# ADC.net
KiCad netlist of a schematic drawn in Altium Designer
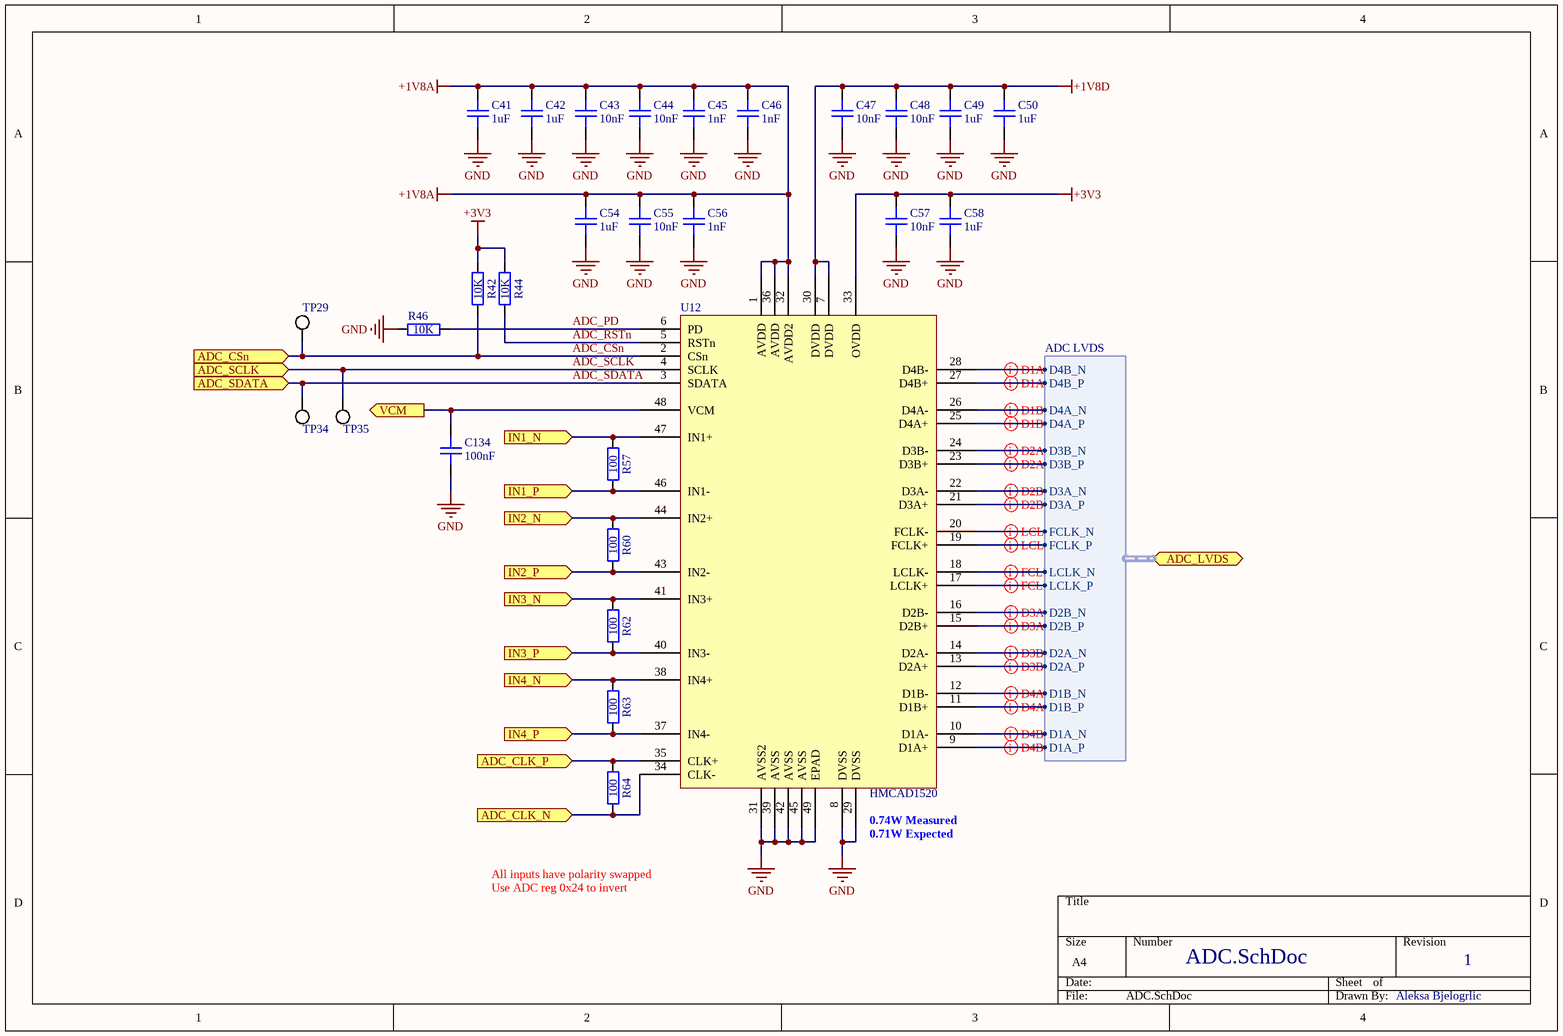
[diagram p0: ADC.SchDoc]

(export (version "E")
  (design (tool "Eeschema 10.0.6"))
  (components
    (comp (ref "C41")
      (value "1uF")
      (footprint "GEN_C_0402")
      (fields
        (field (name "MANUFACTURER") "Murata")
        (field (name "MANUFACTURER PART NUMBER") "GRM155R61E105KA12D")
      )
      (libsource (lib "DSO") (part "CAP 1uF 25V X5R 0402"))
    )
    (comp (ref "C42")
      (value "1uF")
      (footprint "GEN_C_0402")
      (fields
        (field (name "MANUFACTURER") "Murata")
        (field (name "MANUFACTURER PART NUMBER") "GRM155R61E105KA12D")
      )
      (libsource (lib "DSO") (part "CAP 1uF 25V X5R 0402"))
    )
    (comp (ref "C43")
      (value "10nF")
      (footprint "GEN_C_0402")
      (fields
        (field (name "HOUSE PART NUMBER") "C-10nF-0402-002")
        (field (name "MANUFACTURER") "Murata")
        (field (name "MANUFACTURER PART NUMBER") "GRM155R71H103KA88J")
      )
      (libsource (lib "DSO") (part "CAP 10nF 50V X7R 0402"))
    )
    (comp (ref "C44")
      (value "10nF")
      (footprint "GEN_C_0402")
      (fields
        (field (name "HOUSE PART NUMBER") "C-10nF-0402-002")
        (field (name "MANUFACTURER") "Murata")
        (field (name "MANUFACTURER PART NUMBER") "GRM155R71H103KA88J")
      )
      (libsource (lib "DSO") (part "CAP 10nF 50V X7R 0402"))
    )
    (comp (ref "C45")
      (value "1nF")
      (footprint "GEN_C_0402")
      (fields
        (field (name "MANUFACTURER") "Murata")
        (field (name "MANUFACTURER PART NUMBER") "GRM1555C1H102FA01D")
      )
      (libsource (lib "DSO") (part "CAP 1nF 50V C0G 0402"))
    )
    (comp (ref "C46")
      (value "1nF")
      (footprint "GEN_C_0402")
      (fields
        (field (name "MANUFACTURER") "Murata")
        (field (name "MANUFACTURER PART NUMBER") "GRM1555C1H102FA01D")
      )
      (libsource (lib "DSO") (part "CAP 1nF 50V C0G 0402"))
    )
    (comp (ref "C47")
      (value "10nF")
      (footprint "GEN_C_0402")
      (fields
        (field (name "HOUSE PART NUMBER") "C-10nF-0402-002")
        (field (name "MANUFACTURER") "Murata")
        (field (name "MANUFACTURER PART NUMBER") "GRM155R71H103KA88J")
      )
      (libsource (lib "DSO") (part "CAP 10nF 50V X7R 0402"))
    )
    (comp (ref "C48")
      (value "10nF")
      (footprint "GEN_C_0402")
      (fields
        (field (name "HOUSE PART NUMBER") "C-10nF-0402-002")
        (field (name "MANUFACTURER") "Murata")
        (field (name "MANUFACTURER PART NUMBER") "GRM155R71H103KA88J")
      )
      (libsource (lib "DSO") (part "CAP 10nF 50V X7R 0402"))
    )
    (comp (ref "C49")
      (value "1uF")
      (footprint "GEN_C_0402")
      (fields
        (field (name "MANUFACTURER") "Murata")
        (field (name "MANUFACTURER PART NUMBER") "GRM155R61E105KA12D")
      )
      (libsource (lib "DSO") (part "CAP 1uF 25V X5R 0402"))
    )
    (comp (ref "C50")
      (value "1uF")
      (footprint "GEN_C_0402")
      (fields
        (field (name "MANUFACTURER") "Murata")
        (field (name "MANUFACTURER PART NUMBER") "GRM155R61E105KA12D")
      )
      (libsource (lib "DSO") (part "CAP 1uF 25V X5R 0402"))
    )
    (comp (ref "C54")
      (value "1uF")
      (footprint "GEN_C_0402")
      (fields
        (field (name "MANUFACTURER") "Murata")
        (field (name "MANUFACTURER PART NUMBER") "GRM155R61E105KA12D")
      )
      (libsource (lib "DSO") (part "CAP 1uF 25V X5R 0402"))
    )
    (comp (ref "C55")
      (value "10nF")
      (footprint "GEN_C_0402")
      (fields
        (field (name "HOUSE PART NUMBER") "C-10nF-0402-002")
        (field (name "MANUFACTURER") "Murata")
        (field (name "MANUFACTURER PART NUMBER") "GRM155R71H103KA88J")
      )
      (libsource (lib "DSO") (part "CAP 10nF 50V X7R 0402"))
    )
    (comp (ref "C56")
      (value "1nF")
      (footprint "GEN_C_0402")
      (fields
        (field (name "MANUFACTURER") "Murata")
        (field (name "MANUFACTURER PART NUMBER") "GRM1555C1H102FA01D")
      )
      (libsource (lib "DSO") (part "CAP 1nF 50V C0G 0402"))
    )
    (comp (ref "C57")
      (value "10nF")
      (footprint "GEN_C_0402")
      (fields
        (field (name "HOUSE PART NUMBER") "C-10nF-0402-002")
        (field (name "MANUFACTURER") "Murata")
        (field (name "MANUFACTURER PART NUMBER") "GRM155R71H103KA88J")
      )
      (libsource (lib "DSO") (part "CAP 10nF 50V X7R 0402"))
    )
    (comp (ref "C58")
      (value "1uF")
      (footprint "GEN_C_0402")
      (fields
        (field (name "MANUFACTURER") "Murata")
        (field (name "MANUFACTURER PART NUMBER") "GRM155R61E105KA12D")
      )
      (libsource (lib "DSO") (part "CAP 1uF 25V X5R 0402"))
    )
    (comp (ref "C134")
      (value "100nF")
      (footprint "GEN_C_0402")
      (fields
        (field (name "HOUSE PART NUMBER") "C-100nF-0402-002")
        (field (name "MANUFACTURER") "Murata")
        (field (name "MANUFACTURER PART NUMBER") "GCM155R71C104KA55D")
      )
      (libsource (lib "DSO") (part "CAP 100nF 16V X7R 0402"))
    )
    (comp (ref "R42")
      (value "10K")
      (footprint "GEN_R_0402")
      (fields
        (field (name "TOLERANCE") "1%")
        (field (name "MANUFACTURER") "Panasonic")
        (field (name "MANUFACTURER PART NUMBER") "ERJ-2RKF1002X")
      )
      (libsource (lib "DSO") (part "RES 10K OHM 1% 1/10W 0402"))
    )
    (comp (ref "R44")
      (value "10K")
      (footprint "GEN_R_0402")
      (fields
        (field (name "TOLERANCE") "1%")
        (field (name "MANUFACTURER") "Panasonic")
        (field (name "MANUFACTURER PART NUMBER") "ERJ-2RKF1002X")
      )
      (libsource (lib "DSO") (part "RES 10K OHM 1% 1/10W 0402"))
    )
    (comp (ref "R46")
      (value "10K")
      (footprint "GEN_R_0402")
      (fields
        (field (name "TOLERANCE") "1%")
        (field (name "MANUFACTURER") "Panasonic")
        (field (name "MANUFACTURER PART NUMBER") "ERJ-2RKF1002X")
      )
      (libsource (lib "") (part "RES 10K OHM 1% 1/10W 0402_1"))
    )
    (comp (ref "R57")
      (value "100")
      (footprint "GEN_R_0402")
      (fields
        (field (name "TOLERANCE") "1%")
        (field (name "MANUFACTURER") "Yageo")
        (field (name "MANUFACTURER PART NUMBER") "RC0402FR-07100RL")
      )
      (libsource (lib "DSO") (part "RES 100 OHM 1% 1/10W 0402"))
    )
    (comp (ref "R60")
      (value "100")
      (footprint "GEN_R_0402")
      (fields
        (field (name "TOLERANCE") "1%")
        (field (name "MANUFACTURER") "Yageo")
        (field (name "MANUFACTURER PART NUMBER") "RC0402FR-07100RL")
      )
      (libsource (lib "DSO") (part "RES 100 OHM 1% 1/10W 0402"))
    )
    (comp (ref "R62")
      (value "100")
      (footprint "GEN_R_0402")
      (fields
        (field (name "TOLERANCE") "1%")
        (field (name "MANUFACTURER") "Yageo")
        (field (name "MANUFACTURER PART NUMBER") "RC0402FR-07100RL")
      )
      (libsource (lib "DSO") (part "RES 100 OHM 1% 1/10W 0402"))
    )
    (comp (ref "R63")
      (value "100")
      (footprint "GEN_R_0402")
      (fields
        (field (name "TOLERANCE") "1%")
        (field (name "MANUFACTURER") "Yageo")
        (field (name "MANUFACTURER PART NUMBER") "RC0402FR-07100RL")
      )
      (libsource (lib "DSO") (part "RES 100 OHM 1% 1/10W 0402"))
    )
    (comp (ref "R64")
      (value "100")
      (footprint "GEN_R_0402")
      (fields
        (field (name "TOLERANCE") "1%")
        (field (name "MANUFACTURER") "Yageo")
        (field (name "MANUFACTURER PART NUMBER") "RC0402FR-07100RL")
      )
      (libsource (lib "DSO") (part "RES 100 OHM 1% 1/10W 0402"))
    )
    (comp (ref "TP29") (value "PCB") (footprint "GEN_TP_PCB") (libsource (lib "DSO") (part "TP PCB 1mm")))
    (comp (ref "TP34") (value "PCB") (footprint "GEN_TP_PCB") (libsource (lib "DSO") (part "TP PCB 1mm")))
    (comp (ref "TP35") (value "PCB") (footprint "GEN_TP_PCB") (libsource (lib "DSO") (part "TP PCB 1mm")))
    (comp (ref "U12")
      (value "HMCAD1520")
      (footprint "AD_QFN48_LP7")
      (fields (field (name "MANUFACTURER") "Analog Devices"))
      (libsource (lib "DSO") (part "IC ADC HMCAD1520"))
    )
  )
  (nets
    (net (code "3") (name "+1V8A") (class "Default")
      (node (ref "C41") (pin "2") (pinfunction "2_2") (pintype "passive"))
      (node (ref "C42") (pin "2") (pinfunction "2_2") (pintype "passive"))
      (node (ref "C43") (pin "2") (pinfunction "2_2") (pintype "passive"))
      (node (ref "C44") (pin "2") (pinfunction "2_2") (pintype "passive"))
      (node (ref "C45") (pin "2") (pinfunction "2_2") (pintype "passive"))
      (node (ref "C46") (pin "2") (pinfunction "2_2") (pintype "passive"))
      (node (ref "C54") (pin "2") (pinfunction "2_2") (pintype "passive"))
      (node (ref "C55") (pin "2") (pinfunction "2_2") (pintype "passive"))
      (node (ref "C56") (pin "2") (pinfunction "2_2") (pintype "passive"))
      (node (ref "U12") (pin "1") (pinfunction "AVDD_1") (pintype "passive"))
      (node (ref "U12") (pin "32") (pinfunction "AVDD2_32") (pintype "passive"))
      (node (ref "U12") (pin "36") (pinfunction "AVDD_36") (pintype "passive"))
    )
    (net (code "4") (name "+1V8D") (class "Default")
      (node (ref "C47") (pin "2") (pinfunction "2_2") (pintype "passive"))
      (node (ref "C48") (pin "2") (pinfunction "2_2") (pintype "passive"))
      (node (ref "C49") (pin "2") (pinfunction "2_2") (pintype "passive"))
      (node (ref "C50") (pin "2") (pinfunction "2_2") (pintype "passive"))
      (node (ref "U12") (pin "30") (pinfunction "DVDD_30") (pintype "passive"))
      (node (ref "U12") (pin "7") (pinfunction "DVDD_7") (pintype "passive"))
    )
    (net (code "5") (name "+3V3") (class "Default")
      (node (ref "C57") (pin "2") (pinfunction "2_2") (pintype "passive"))
      (node (ref "C58") (pin "2") (pinfunction "2_2") (pintype "passive"))
      (node (ref "R42") (pin "2") (pinfunction "2_2") (pintype "passive"))
      (node (ref "R44") (pin "2") (pinfunction "2_2") (pintype "passive"))
      (node (ref "U12") (pin "33") (pinfunction "OVDD_33") (pintype "passive"))
    )
    (net (code "6") (name "/ADC_CLK_N") (class "Default")
      (node (ref "R64") (pin "1") (pinfunction "1_1") (pintype "passive"))
      (node (ref "U12") (pin "34") (pinfunction "CLK-_34") (pintype "passive"))
    )
    (net (code "7") (name "/ADC_CLK_P") (class "Default")
      (node (ref "R64") (pin "2") (pinfunction "2_2") (pintype "passive"))
      (node (ref "U12") (pin "35") (pinfunction "CLK+_35") (pintype "passive"))
    )
    (net (code "8") (name "/ADC_CSn") (class "Default")
      (node (ref "R42") (pin "1") (pinfunction "1_1") (pintype "passive"))
      (node (ref "TP29") (pin "1") (pinfunction "1_1") (pintype "passive"))
      (node (ref "U12") (pin "2") (pinfunction "CSn_2") (pintype "passive"))
    )
    (net (code "9") (name "/ADC_PD") (class "Default")
      (node (ref "R46") (pin "1") (pinfunction "1_1") (pintype "passive"))
      (node (ref "U12") (pin "6") (pinfunction "PD_6") (pintype "passive"))
    )
    (net (code "10") (name "/ADC_RSTn") (class "Default")
      (node (ref "R44") (pin "1") (pinfunction "1_1") (pintype "passive"))
      (node (ref "U12") (pin "5") (pinfunction "RSTn_5") (pintype "passive"))
    )
    (net (code "11") (name "/ADC_SCLK") (class "Default")
      (node (ref "TP35") (pin "1") (pinfunction "1_1") (pintype "passive"))
      (node (ref "U12") (pin "4") (pinfunction "SCLK_4") (pintype "passive"))
    )
    (net (code "12") (name "/ADC_SDATA") (class "Default")
      (node (ref "TP34") (pin "1") (pinfunction "1_1") (pintype "passive"))
      (node (ref "U12") (pin "3") (pinfunction "SDATA_3") (pintype "passive"))
    )
    (net (code "13") (name "/D1A_N") (class "Default")
      (node (ref "U12") (pin "10") (pinfunction "D1A-_10") (pintype "passive"))
    )
    (net (code "14") (name "/D1A_P") (class "Default")
      (node (ref "U12") (pin "9") (pinfunction "D1A+_9") (pintype "passive"))
    )
    (net (code "15") (name "/D1B_N") (class "Default")
      (node (ref "U12") (pin "12") (pinfunction "D1B-_12") (pintype "passive"))
    )
    (net (code "16") (name "/D1B_P") (class "Default")
      (node (ref "U12") (pin "11") (pinfunction "D1B+_11") (pintype "passive"))
    )
    (net (code "17") (name "/D2A_N") (class "Default")
      (node (ref "U12") (pin "14") (pinfunction "D2A-_14") (pintype "passive"))
    )
    (net (code "18") (name "/D2A_P") (class "Default")
      (node (ref "U12") (pin "13") (pinfunction "D2A+_13") (pintype "passive"))
    )
    (net (code "19") (name "/D2B_N") (class "Default")
      (node (ref "U12") (pin "16") (pinfunction "D2B-_16") (pintype "passive"))
    )
    (net (code "20") (name "/D2B_P") (class "Default")
      (node (ref "U12") (pin "15") (pinfunction "D2B+_15") (pintype "passive"))
    )
    (net (code "21") (name "/D3A_N") (class "Default")
      (node (ref "U12") (pin "22") (pinfunction "D3A-_22") (pintype "passive"))
    )
    (net (code "22") (name "/D3A_P") (class "Default")
      (node (ref "U12") (pin "21") (pinfunction "D3A+_21") (pintype "passive"))
    )
    (net (code "23") (name "/D3B_N") (class "Default")
      (node (ref "U12") (pin "24") (pinfunction "D3B-_24") (pintype "passive"))
    )
    (net (code "24") (name "/D3B_P") (class "Default")
      (node (ref "U12") (pin "23") (pinfunction "D3B+_23") (pintype "passive"))
    )
    (net (code "25") (name "/D4A_N") (class "Default")
      (node (ref "U12") (pin "26") (pinfunction "D4A-_26") (pintype "passive"))
    )
    (net (code "26") (name "/D4A_P") (class "Default")
      (node (ref "U12") (pin "25") (pinfunction "D4A+_25") (pintype "passive"))
    )
    (net (code "27") (name "/D4B_N") (class "Default")
      (node (ref "U12") (pin "28") (pinfunction "D4B-_28") (pintype "passive"))
    )
    (net (code "28") (name "/D4B_P") (class "Default")
      (node (ref "U12") (pin "27") (pinfunction "D4B+_27") (pintype "passive"))
    )
    (net (code "29") (name "/FCLK_N") (class "Default")
      (node (ref "U12") (pin "20") (pinfunction "FCLK-_20") (pintype "passive"))
    )
    (net (code "30") (name "/FCLK_P") (class "Default")
      (node (ref "U12") (pin "19") (pinfunction "FCLK+_19") (pintype "passive"))
    )
    (net (code "31") (name "/IN1_N") (class "Default")
      (node (ref "R57") (pin "2") (pinfunction "2_2") (pintype "passive"))
      (node (ref "U12") (pin "47") (pinfunction "IN1+_47") (pintype "passive"))
    )
    (net (code "32") (name "/IN1_P") (class "Default")
      (node (ref "R57") (pin "1") (pinfunction "1_1") (pintype "passive"))
      (node (ref "U12") (pin "46") (pinfunction "IN1-_46") (pintype "passive"))
    )
    (net (code "33") (name "/IN2_N") (class "Default")
      (node (ref "R60") (pin "2") (pinfunction "2_2") (pintype "passive"))
      (node (ref "U12") (pin "44") (pinfunction "IN2+_44") (pintype "passive"))
    )
    (net (code "34") (name "/IN2_P") (class "Default")
      (node (ref "R60") (pin "1") (pinfunction "1_1") (pintype "passive"))
      (node (ref "U12") (pin "43") (pinfunction "IN2-_43") (pintype "passive"))
    )
    (net (code "35") (name "/IN3_N") (class "Default")
      (node (ref "R62") (pin "2") (pinfunction "2_2") (pintype "passive"))
      (node (ref "U12") (pin "41") (pinfunction "IN3+_41") (pintype "passive"))
    )
    (net (code "36") (name "/IN3_P") (class "Default")
      (node (ref "R62") (pin "1") (pinfunction "1_1") (pintype "passive"))
      (node (ref "U12") (pin "40") (pinfunction "IN3-_40") (pintype "passive"))
    )
    (net (code "37") (name "/IN4_N") (class "Default")
      (node (ref "R63") (pin "2") (pinfunction "2_2") (pintype "passive"))
      (node (ref "U12") (pin "38") (pinfunction "IN4+_38") (pintype "passive"))
    )
    (net (code "38") (name "/IN4_P") (class "Default")
      (node (ref "R63") (pin "1") (pinfunction "1_1") (pintype "passive"))
      (node (ref "U12") (pin "37") (pinfunction "IN4-_37") (pintype "passive"))
    )
    (net (code "39") (name "/LCLK_N") (class "Default")
      (node (ref "U12") (pin "18") (pinfunction "LCLK-_18") (pintype "passive"))
    )
    (net (code "40") (name "/LCLK_P") (class "Default")
      (node (ref "U12") (pin "17") (pinfunction "LCLK+_17") (pintype "passive"))
    )
    (net (code "41") (name "/VCM") (class "Default")
      (node (ref "C134") (pin "2") (pinfunction "2_2") (pintype "passive"))
      (node (ref "U12") (pin "48") (pinfunction "VCM_48") (pintype "passive"))
    )
    (net (code "43") (name "GND") (class "Default")
      (node (ref "C134") (pin "1") (pinfunction "1_1") (pintype "passive"))
      (node (ref "C41") (pin "1") (pinfunction "1_1") (pintype "passive"))
      (node (ref "C42") (pin "1") (pinfunction "1_1") (pintype "passive"))
      (node (ref "C43") (pin "1") (pinfunction "1_1") (pintype "passive"))
      (node (ref "C44") (pin "1") (pinfunction "1_1") (pintype "passive"))
      (node (ref "C45") (pin "1") (pinfunction "1_1") (pintype "passive"))
      (node (ref "C46") (pin "1") (pinfunction "1_1") (pintype "passive"))
      (node (ref "C47") (pin "1") (pinfunction "1_1") (pintype "passive"))
      (node (ref "C48") (pin "1") (pinfunction "1_1") (pintype "passive"))
      (node (ref "C49") (pin "1") (pinfunction "1_1") (pintype "passive"))
      (node (ref "C50") (pin "1") (pinfunction "1_1") (pintype "passive"))
      (node (ref "C54") (pin "1") (pinfunction "1_1") (pintype "passive"))
      (node (ref "C55") (pin "1") (pinfunction "1_1") (pintype "passive"))
      (node (ref "C56") (pin "1") (pinfunction "1_1") (pintype "passive"))
      (node (ref "C57") (pin "1") (pinfunction "1_1") (pintype "passive"))
      (node (ref "C58") (pin "1") (pinfunction "1_1") (pintype "passive"))
      (node (ref "R46") (pin "2") (pinfunction "2_2") (pintype "passive"))
      (node (ref "U12") (pin "29") (pinfunction "DVSS_29") (pintype "passive"))
      (node (ref "U12") (pin "31") (pinfunction "AVSS2_31") (pintype "passive"))
      (node (ref "U12") (pin "39") (pinfunction "AVSS_39") (pintype "passive"))
      (node (ref "U12") (pin "42") (pinfunction "AVSS_42") (pintype "passive"))
      (node (ref "U12") (pin "45") (pinfunction "AVSS_45") (pintype "passive"))
      (node (ref "U12") (pin "49") (pinfunction "EPAD_49") (pintype "passive"))
      (node (ref "U12") (pin "8") (pinfunction "DVSS_8") (pintype "passive"))
    )
  )
)
